# Microcontroller.net
KiCad netlist of a schematic drawn in Altium Designer
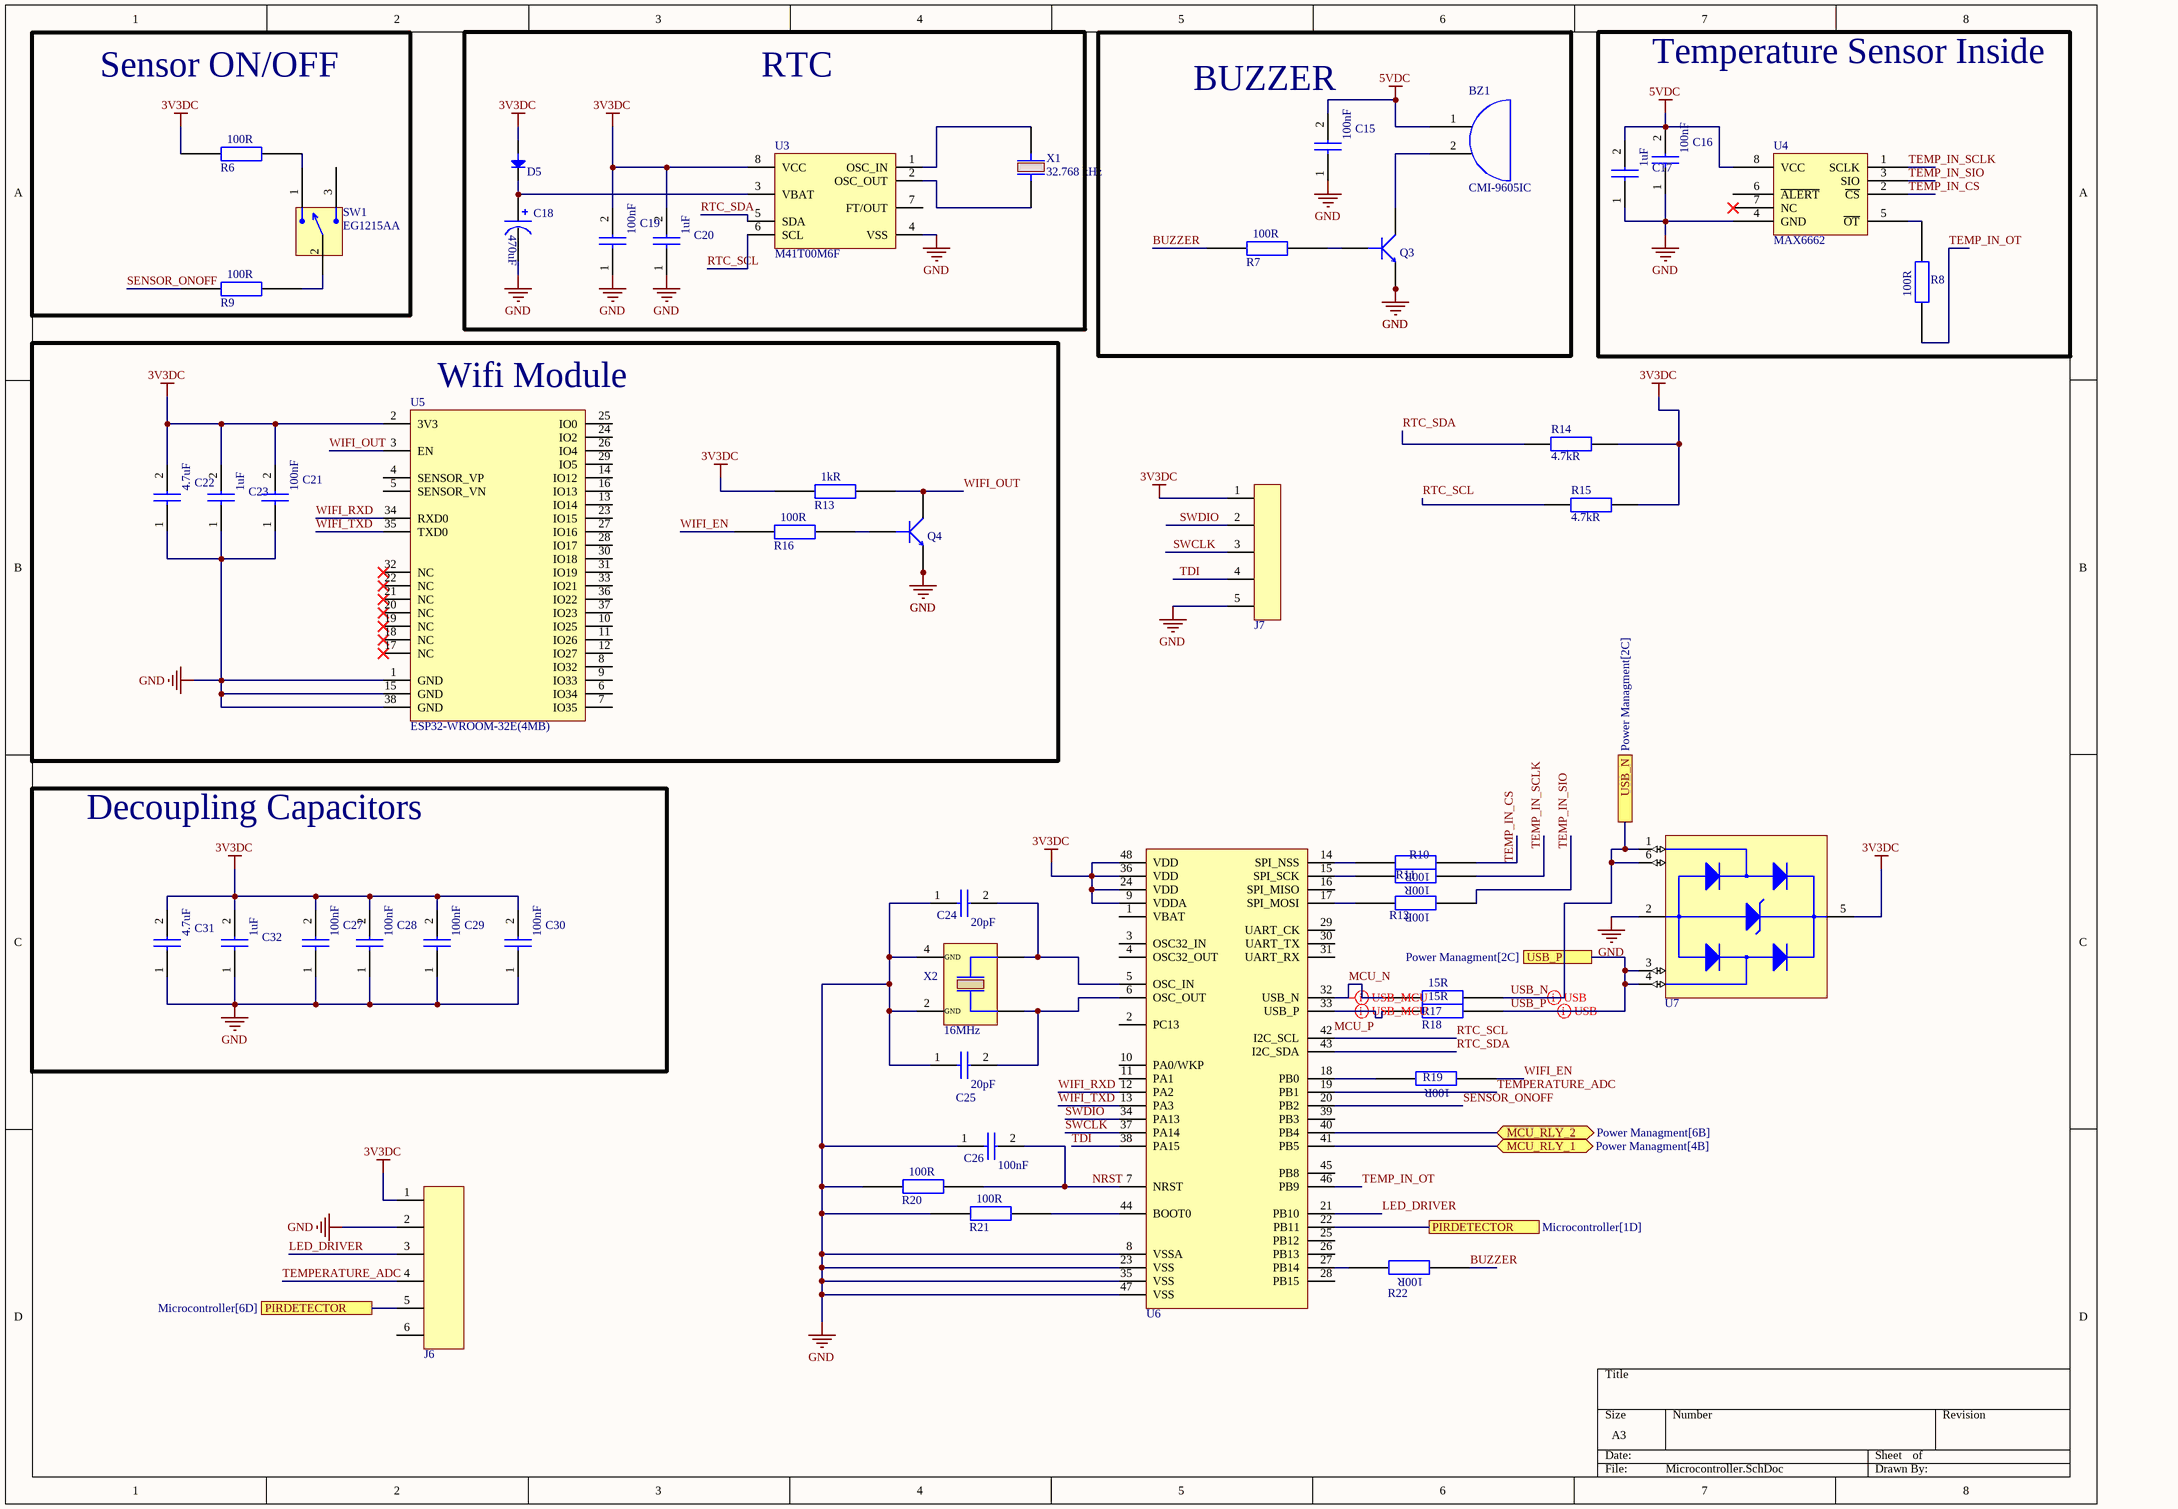
[diagram p0: Microcontroller.SchDoc]

(export (version "E")
  (design (tool "Eeschema 10.0.6"))
  (components
    (comp (ref "BZ1")
      (value "CMI-9605IC-0580T")
      (footprint "CMI-9605IC-0580T")
      (description "Audio Buzzer Magnetic 3VDC 7VDC 30mA 5VDC 85dB 2600Hz to 2800Hz Through Hole Pin Box")
      (fields
        (field (name "MANUFACTURER") "CUI Devices")
        (field (name "CASE/PACKAGE") "CMI-9605IC")
        (field (name "DEESIGNED BY") "Mert Ali Şentürl")
      )
      (libsource (lib "bowtie") (part "CMI-9605IC-0580T"))
    )
    (comp (ref "C15")
      (value "CL21B104KBCNNNC")
      (footprint "CAP_0805")
      (description "CAP CER 100nF %10 0603 SMD")
      (fields
        (field (name "MANUFACTURER") "Samsung")
        (field (name "TOLERANCE") "10%")
        (field (name "DESIGNED BY") "BERK")
      )
      (libsource (lib "bowtie") (part "CAP CER 0805 100nF %10"))
    )
    (comp (ref "C16")
      (value "CL21B104KBCNNNC")
      (footprint "CAP_0805")
      (description "CAP CER 100nF %10 0603 SMD")
      (fields
        (field (name "MANUFACTURER") "Samsung")
        (field (name "TOLERANCE") "10%")
        (field (name "DESIGNED BY") "BERK")
      )
      (libsource (lib "bowtie") (part "CAP CER 0805 100nF %10"))
    )
    (comp (ref "C17")
      (value "CL21B105KBFNNNE")
      (footprint "CAP_0805")
      (description "CAP CER 1uF %10 0805")
      (fields
        (field (name "MANUFACTURER") "Samsung")
        (field (name "TOLERANCE") "10%")
        (field (name "DESIGNED BY") "BERK")
      )
      (libsource (lib "bowtie") (part "CAP CER 0805 1uF %10"))
    )
    (comp (ref "C18")
      (value "CAP ALU ELEC 470uF 50V")
      (footprint "CAP_RADIAL_D10_P5")
      (description "Cap, 470UF, 50V, Alu Elec, Radial")
      (fields
        (field (name "MANUFACTURER") "KEMET")
        (field (name "MANUFACTURER PART NUMBER") "ESH477M050AH4AA")
        (field (name "DESIGNED BY") "Mert Ali Şentürk")
      )
      (libsource (lib "bowtie") (part "CAP ALU ELEC 470uF 50V"))
    )
    (comp (ref "C19")
      (value "CL21B104KBCNNNC")
      (footprint "CAP_0805")
      (description "CAP CER 100nF %10 0603 SMD")
      (fields
        (field (name "MANUFACTURER") "Samsung")
        (field (name "TOLERANCE") "10%")
        (field (name "DESIGNED BY") "BERK")
      )
      (libsource (lib "bowtie") (part "CAP CER 0805 100nF %10"))
    )
    (comp (ref "C20")
      (value "CL21B105KBFNNNE")
      (footprint "CAP_0805")
      (description "CAP CER 1uF %10 0805")
      (fields
        (field (name "MANUFACTURER") "Samsung")
        (field (name "TOLERANCE") "10%")
        (field (name "DESIGNED BY") "BERK")
      )
      (libsource (lib "bowtie") (part "CAP CER 0805 1uF %10"))
    )
    (comp (ref "C21")
      (value "CL21B104KBCNNNC")
      (footprint "CAP_0805")
      (description "CAP CER 100nF %10 0603 SMD")
      (fields
        (field (name "MANUFACTURER") "Samsung")
        (field (name "TOLERANCE") "10%")
        (field (name "DESIGNED BY") "BERK")
      )
      (libsource (lib "bowtie") (part "CAP CER 0805 100nF %10"))
    )
    (comp (ref "C22")
      (value "CL21A475KAQNNNE")
      (footprint "CAP_0805")
      (description "CAP CER 4.7uF %10 0805")
      (fields
        (field (name "MANUFACTURER") "Samsung")
        (field (name "TOLERANCE") "10%")
        (field (name "DESIGNED BY") "BERK")
      )
      (libsource (lib "bowtie") (part "CAP CER 0805 4.7uF %10"))
    )
    (comp (ref "C23")
      (value "CL21B105KBFNNNE")
      (footprint "CAP_0805")
      (description "CAP CER 1uF %10 0805")
      (fields
        (field (name "MANUFACTURER") "Samsung")
        (field (name "TOLERANCE") "10%")
        (field (name "DESIGNED BY") "BERK")
      )
      (libsource (lib "bowtie") (part "CAP CER 0805 1uF %10"))
    )
    (comp (ref "C24")
      (value "CL10C200JB8NNNC")
      (footprint "CAP_0603")
      (description "CAP CER 20pF %5 0603 SMD")
      (fields
        (field (name "MANUFACTURER") "Samsung")
        (field (name "TOLERANCE") "5%")
        (field (name "DESIGNED BY") "BERK")
      )
      (libsource (lib "bowtie") (part "CAP CER 0603 20pF %5"))
    )
    (comp (ref "C25")
      (value "CL10C200JB8NNNC")
      (footprint "CAP_0603")
      (description "CAP CER 20pF %5 0603 SMD")
      (fields
        (field (name "MANUFACTURER") "Samsung")
        (field (name "TOLERANCE") "5%")
        (field (name "DESIGNED BY") "BERK")
      )
      (libsource (lib "bowtie") (part "CAP CER 0603 20pF %5"))
    )
    (comp (ref "C26")
      (value "CL21B104KBCNNNC")
      (footprint "CAP_0805")
      (description "CAP CER 100nF %10 0603 SMD")
      (fields
        (field (name "MANUFACTURER") "Samsung")
        (field (name "TOLERANCE") "10%")
        (field (name "DESIGNED BY") "BERK")
      )
      (libsource (lib "bowtie") (part "CAP CER 0805 100nF %10"))
    )
    (comp (ref "C27")
      (value "CL21B104KBCNNNC")
      (footprint "CAP_0805")
      (description "CAP CER 100nF %10 0603 SMD")
      (fields
        (field (name "MANUFACTURER") "Samsung")
        (field (name "TOLERANCE") "10%")
        (field (name "DESIGNED BY") "BERK")
      )
      (libsource (lib "bowtie") (part "CAP CER 0805 100nF %10"))
    )
    (comp (ref "C28")
      (value "CL21B104KBCNNNC")
      (footprint "CAP_0805")
      (description "CAP CER 100nF %10 0603 SMD")
      (fields
        (field (name "MANUFACTURER") "Samsung")
        (field (name "TOLERANCE") "10%")
        (field (name "DESIGNED BY") "BERK")
      )
      (libsource (lib "bowtie") (part "CAP CER 0805 100nF %10"))
    )
    (comp (ref "C29")
      (value "CL21B104KBCNNNC")
      (footprint "CAP_0805")
      (description "CAP CER 100nF %10 0603 SMD")
      (fields
        (field (name "MANUFACTURER") "Samsung")
        (field (name "TOLERANCE") "10%")
        (field (name "DESIGNED BY") "BERK")
      )
      (libsource (lib "bowtie") (part "CAP CER 0805 100nF %10"))
    )
    (comp (ref "C30")
      (value "CL21B104KBCNNNC")
      (footprint "CAP_0805")
      (description "CAP CER 100nF %10 0603 SMD")
      (fields
        (field (name "MANUFACTURER") "Samsung")
        (field (name "TOLERANCE") "10%")
        (field (name "DESIGNED BY") "BERK")
      )
      (libsource (lib "bowtie") (part "CAP CER 0805 100nF %10"))
    )
    (comp (ref "C31")
      (value "CL21A475KAQNNNE")
      (footprint "CAP_0805")
      (description "CAP CER 4.7uF %10 0805")
      (fields
        (field (name "MANUFACTURER") "Samsung")
        (field (name "TOLERANCE") "10%")
        (field (name "DESIGNED BY") "BERK")
      )
      (libsource (lib "bowtie") (part "CAP CER 0805 4.7uF %10"))
    )
    (comp (ref "C32")
      (value "CL21B105KBFNNNE")
      (footprint "CAP_0805")
      (description "CAP CER 1uF %10 0805")
      (fields
        (field (name "MANUFACTURER") "Samsung")
        (field (name "TOLERANCE") "10%")
        (field (name "DESIGNED BY") "BERK")
      )
      (libsource (lib "bowtie") (part "CAP CER 0805 1uF %10"))
    )
    (comp (ref "D5")
      (value "1N4148WS")
      (footprint "SOD-323F")
      (description "Diode, Single, 75 V, 150 mA, 1 V, 4 ns")
      (fields
        (field (name "MANUFACTURER") "ON Semiconductor / Fairchild")
        (field (name "DESIGNED BY") "BERK")
      )
      (libsource (lib "bowtie") (part "1N4148WS"))
    )
    (comp (ref "J6")
      (value "64800611622")
      (footprint "64800611622")
      (description "1.50mm 6PIN Connector")
      (fields (field (name "MANUFACTURER") "Wurth Electronics"))
      (libsource (lib "bowtie") (part "64800611622_conn_6pin"))
    )
    (comp (ref "J7")
      (value "SMH-105-02-L-S")
      (footprint "PINHEADER1X5_RA")
      (description ".100 C.L. HORIZONTAL SMT SOCKET")
      (fields (field (name "MANUFACTURER") "Samtec") (field (name "DESIGNED BY") "BERK"))
      (libsource (lib "bowtie") (part "SMH-105-02-L-S"))
    )
    (comp (ref "Q3")
      (value "MMBT3904-7-F")
      (footprint "SOT23-F")
      (description "Transistor General Purpose BJT NPN 40 Volt 0.2A Automotive 3-Pin SOT-23")
      (fields (field (name "MANUFACTURER") "Diodes Zetex") (field (name "DESIGNED BY") "BERK"))
      (libsource (lib "bowtie") (part "MMBT3904-7-F"))
    )
    (comp (ref "Q4")
      (value "MMBT3904-7-F")
      (footprint "SOT23-F")
      (description "Transistor General Purpose BJT NPN 40 Volt 0.2A Automotive 3-Pin SOT-23")
      (fields (field (name "MANUFACTURER") "Diodes Zetex") (field (name "DESIGNED BY") "BERK"))
      (libsource (lib "bowtie") (part "MMBT3904-7-F"))
    )
    (comp (ref "R6")
      (value "RC0603JR-07100RL")
      (footprint "RES_0603")
      (description "RES 100 %5 OHM 0603 SMD")
      (fields
        (field (name "MANUFACTURER") "Yageo")
        (field (name "TOLERANCE") "5%")
        (field (name "DESIGNED BY") "BERK")
      )
      (libsource (lib "bowtie") (part "RES 0603 100R %5"))
    )
    (comp (ref "R7")
      (value "RC0603JR-07100RL")
      (footprint "RES_0603")
      (description "RES 100 %5 OHM 0603 SMD")
      (fields
        (field (name "MANUFACTURER") "Yageo")
        (field (name "TOLERANCE") "5%")
        (field (name "DESIGNED BY") "BERK")
      )
      (libsource (lib "bowtie") (part "RES 0603 100R %5"))
    )
    (comp (ref "R8")
      (value "RC0603JR-07100RL")
      (footprint "RES_0603")
      (description "RES 100 %5 OHM 0603 SMD")
      (fields
        (field (name "MANUFACTURER") "Yageo")
        (field (name "TOLERANCE") "5%")
        (field (name "DESIGNED BY") "BERK")
      )
      (libsource (lib "bowtie") (part "RES 0603 100R %5"))
    )
    (comp (ref "R9")
      (value "RC0603JR-07100RL")
      (footprint "RES_0603")
      (description "RES 100 %5 OHM 0603 SMD")
      (fields
        (field (name "MANUFACTURER") "Yageo")
        (field (name "TOLERANCE") "5%")
        (field (name "DESIGNED BY") "BERK")
      )
      (libsource (lib "bowtie") (part "RES 0603 100R %5"))
    )
    (comp (ref "R10")
      (value "RC0603JR-07100RL")
      (footprint "RES_0603")
      (description "RES 100 %5 OHM 0603 SMD")
      (fields
        (field (name "MANUFACTURER") "Yageo")
        (field (name "TOLERANCE") "5%")
        (field (name "DESIGNED BY") "BERK")
      )
      (libsource (lib "bowtie") (part "RES 0603 100R %5"))
    )
    (comp (ref "R11")
      (value "RC0603JR-07100RL")
      (footprint "RES_0603")
      (description "RES 100 %5 OHM 0603 SMD")
      (fields
        (field (name "MANUFACTURER") "Yageo")
        (field (name "TOLERANCE") "5%")
        (field (name "DESIGNED BY") "BERK")
      )
      (libsource (lib "bowtie") (part "RES 0603 100R %5"))
    )
    (comp (ref "R12")
      (value "RC0603JR-07100RL")
      (footprint "RES_0603")
      (description "RES 100 %5 OHM 0603 SMD")
      (fields
        (field (name "MANUFACTURER") "Yageo")
        (field (name "TOLERANCE") "5%")
        (field (name "DESIGNED BY") "BERK")
      )
      (libsource (lib "bowtie") (part "RES 0603 100R %5"))
    )
    (comp (ref "R13")
      (value "RC0603FR-0710KL")
      (footprint "RES_0603")
      (description "RES 1K %1 OHM 0603 SMD")
      (fields
        (field (name "MANUFACTURER") "Yageo")
        (field (name "MANUFACTURER PART NUMBER") "RC0603JR-071KL")
        (field (name "DESIGNED BY") "BERK")
      )
      (libsource (lib "bowtie") (part "RES 0603 1kR %1"))
    )
    (comp (ref "R14")
      (value "RC0603JR-074K7L")
      (footprint "RES_0603")
      (description "RES 4K7 %5 OHM 0603 SMD")
      (fields
        (field (name "MANUFACTURER") "Yageo")
        (field (name "TOLERANCE") "5%")
        (field (name "RESISTANCE") "4.7kR")
        (field (name "DESIGNED BY") "BERK")
      )
      (libsource (lib "bowtie") (part "RES 4K7 OHM 0603"))
    )
    (comp (ref "R15")
      (value "RC0603JR-074K7L")
      (footprint "RES_0603")
      (description "RES 4K7 %5 OHM 0603 SMD")
      (fields
        (field (name "MANUFACTURER") "Yageo")
        (field (name "TOLERANCE") "5%")
        (field (name "RESISTANCE") "4.7kR")
        (field (name "DESIGNED BY") "BERK")
      )
      (libsource (lib "bowtie") (part "RES 4K7 OHM 0603"))
    )
    (comp (ref "R16")
      (value "RC0603JR-07100RL")
      (footprint "RES_0603")
      (description "RES 100 %5 OHM 0603 SMD")
      (fields
        (field (name "MANUFACTURER") "Yageo")
        (field (name "TOLERANCE") "5%")
        (field (name "DESIGNED BY") "BERK")
      )
      (libsource (lib "bowtie") (part "RES 0603 100R %5"))
    )
    (comp (ref "R17")
      (value "RC0603JR-0715RL")
      (footprint "RES_0603")
      (description "RES 15 %5 OHM 0603 SMD")
      (fields
        (field (name "MANUFACTURER") "Yageo")
        (field (name "TOLERANCE") "5%")
        (field (name "DESIGNED BY") "BERK")
      )
      (libsource (lib "bowtie") (part "RES 0603 15R %5"))
    )
    (comp (ref "R18")
      (value "RC0603JR-0715RL")
      (footprint "RES_0603")
      (description "RES 15 %5 OHM 0603 SMD")
      (fields
        (field (name "MANUFACTURER") "Yageo")
        (field (name "TOLERANCE") "5%")
        (field (name "DESIGNED BY") "BERK")
      )
      (libsource (lib "bowtie") (part "RES 0603 15R %5"))
    )
    (comp (ref "R19")
      (value "RC0603JR-07100RL")
      (footprint "RES_0603")
      (description "RES 100 %5 OHM 0603 SMD")
      (fields
        (field (name "MANUFACTURER") "Yageo")
        (field (name "TOLERANCE") "5%")
        (field (name "DESIGNED BY") "BERK")
      )
      (libsource (lib "bowtie") (part "RES 0603 100R %5"))
    )
    (comp (ref "R20")
      (value "RC0603JR-07100RL")
      (footprint "RES_0603")
      (description "RES 100 %5 OHM 0603 SMD")
      (fields
        (field (name "MANUFACTURER") "Yageo")
        (field (name "TOLERANCE") "5%")
        (field (name "DESIGNED BY") "BERK")
      )
      (libsource (lib "bowtie") (part "RES 0603 100R %5"))
    )
    (comp (ref "R21")
      (value "RC0603JR-07100RL")
      (footprint "RES_0603")
      (description "RES 100 %5 OHM 0603 SMD")
      (fields
        (field (name "MANUFACTURER") "Yageo")
        (field (name "TOLERANCE") "5%")
        (field (name "DESIGNED BY") "BERK")
      )
      (libsource (lib "bowtie") (part "RES 0603 100R %5"))
    )
    (comp (ref "R22")
      (value "RC0603JR-07100RL")
      (footprint "RES_0603")
      (description "RES 100 %5 OHM 0603 SMD")
      (fields
        (field (name "MANUFACTURER") "Yageo")
        (field (name "TOLERANCE") "5%")
        (field (name "DESIGNED BY") "BERK")
      )
      (libsource (lib "bowtie") (part "RES 0603 100R %5"))
    )
    (comp (ref "SW1")
      (value "EG1215AA")
      (footprint "EG1215AA")
      (description "Slide Switch, SPDT, 0.025A, 24V, SMD")
      (fields (field (name "MANUFACTURER") "E-Switch") (field (name "DESIGNED BY") "Mert Ali Şentürk"))
      (libsource (lib "bowtie") (part "EG1215AA"))
    )
    (comp (ref "U3")
      (value "M41T00M6F")
      (footprint "SOIC-8")
      (description "Real-time Clocks Clock/Calendar I2C, 2-Wire Serial 70uA @ 2V ~ 5.5V SOIC-8_150mil RoHS")
      (fields
        (field (name "MANUFACTURER") "STMicroelectronics")
        (field (name "DESIGNED BY") "Mert Ali Şentürk")
      )
      (libsource (lib "bowtie") (part "M41T00M6F"))
    )
    (comp (ref "U4")
      (value "MAX6662")
      (footprint "SOIC-8")
      (description "Temp Sensor Digital Serial (3-Wire, SPI) 8-Pin SOIC N Tube")
      (fields
        (field (name "MANUFACTURER") "Maxim")
        (field (name "MANUFACTURER PART NUMBER") "MAX6662MSA+")
        (field (name "DESIGNED BY") "Mert Ali Şentürk")
      )
      (libsource (lib "bowtie") (part "MAX6662"))
    )
    (comp (ref "U5")
      (value "ESP32-WROOM-32E(4MB)")
      (footprint "ESP32WROOM32D/E")
      (description "SMD module, ESP32-D0WD-V3, ESP32 ECO V3, 4 MB SPI flash, PCB antenna")
      (fields
        (field (name "MANUFACTURER") "Espressif Systems")
        (field (name "MANUFACTURER PART NUMBER") "ESP32-WROOM-32E(M113EH3200PH3Q0)")
        (field (name "DESIGNED BY") "Mert Ali Şentürk")
      )
      (libsource (lib "bowtie") (part "ESP32-WROOM-32E(4MB)"))
    )
    (comp (ref "U6")
      (value "STM32F103C6T6A")
      (footprint "LQFP-48")
      (description "MCU 32-bit STM32F ARM Cortex M3 RISC 32KB Flash 2.5V/3.3V 48-Pin LQFP Tray")
      (fields
        (field (name "MANUFACTURER") "STMicroelectronics")
        (field (name "DESIGNED BY") "Mert Ali Şentürk")
      )
      (libsource (lib "bowtie") (part "STM32F103C6T6A"))
    )
    (comp (ref "U7")
      (value "USBLC6-2SC6")
      (footprint "SOT23-6L")
      (description "TVS DIODE 5.25V 17V SOT23-6")
      (fields (field (name "MANUFACTURER") "STMicroelectronics") (field (name "DESIGNED BY") "BERK"))
      (libsource (lib "bowtie") (part "USB PROTECTION"))
    )
    (comp (ref "X1")
      (value "ABS05-32.768KHZ-T")
      (footprint "ABS05")
      (description "Crystal, 32.768 kHz, SMD, 1.6mm x 1mm, 12.5 pF, 20 ppm, ABS05 Series")
      (fields
        (field (name "MANUFACTURER") "Abracon")
        (field (name "TOLERANCE") "20ppm")
        (field (name "OPERATING FREQUENCY") "32.768 kHz")
        (field (name "DESIGNED BY") "BERK")
      )
      (libsource (lib "bowtie") (part "CRYSTAL 32768kHZ"))
    )
    (comp (ref "X2")
      (value "ECS-160-20-30B-TR")
      (footprint "ECS")
      (description "CRYSTAL 16.0000MHZ 20PF SMD")
      (fields
        (field (name "MANUFACTURER") "ECS International")
        (field (name "TOLERANCE") "50ppm")
        (field (name "FREQUENCY") "16MHz")
        (field (name "DESIGNED BY") "BERK")
      )
      (libsource (lib "bowtie") (part "CRYSTAL 16MHz"))
    )
  )
  (nets
    (net (code "1") (name "/BUZZER") (class "Default")
      (node (ref "R22") (pin "1") (pinfunction "1_1") (pintype "passive"))
      (node (ref "R7") (pin "1") (pinfunction "1_1") (pintype "passive"))
    )
    (net (code "2") (name "/LED_DRIVER") (class "Default")
      (node (ref "J6") (pin "3") (pintype "power_in"))
      (node (ref "U6") (pin "21") (pinfunction "PB10_21") (pintype "passive"))
    )
    (net (code "3") (name "/MCU_N") (class "Default")
      (node (ref "R17") (pin "1") (pinfunction "1_1") (pintype "passive"))
      (node (ref "U6") (pin "32") (pinfunction "USB_N_32") (pintype "passive"))
    )
    (net (code "4") (name "/MCU_P") (class "Default")
      (node (ref "R18") (pin "1") (pinfunction "1_1") (pintype "passive"))
      (node (ref "U6") (pin "33") (pinfunction "USB_P_33") (pintype "passive"))
    )
    (net (code "5") (name "/MCU_RLY_1") (class "Default")
      (node (ref "U6") (pin "41") (pinfunction "PB5_41") (pintype "passive"))
    )
    (net (code "6") (name "/MCU_RLY_2") (class "Default")
      (node (ref "U6") (pin "40") (pinfunction "PB4_40") (pintype "passive"))
    )
    (net (code "7") (name "/NRST") (class "Default")
      (node (ref "C26") (pin "2") (pinfunction "2_2") (pintype "passive"))
      (node (ref "R20") (pin "2") (pinfunction "2_2") (pintype "passive"))
      (node (ref "U6") (pin "7") (pinfunction "NRST_7") (pintype "passive"))
    )
    (net (code "8") (name "/PIRDETECTOR") (class "Default")
      (node (ref "J6") (pin "5") (pintype "power_in"))
      (node (ref "U6") (pin "22") (pinfunction "PB11_22") (pintype "passive"))
    )
    (net (code "9") (name "/RTC_SCL") (class "Default")
      (node (ref "R15") (pin "1") (pinfunction "1_1") (pintype "passive"))
      (node (ref "U3") (pin "6") (pinfunction "SCL_6") (pintype "passive"))
      (node (ref "U6") (pin "42") (pinfunction "I2C_SCL_42") (pintype "passive"))
    )
    (net (code "10") (name "/RTC_SDA") (class "Default")
      (node (ref "R14") (pin "1") (pinfunction "1_1") (pintype "passive"))
      (node (ref "U3") (pin "5") (pinfunction "SDA_5") (pintype "passive"))
      (node (ref "U6") (pin "43") (pinfunction "I2C_SDA_43") (pintype "passive"))
    )
    (net (code "11") (name "/SENSOR_ONOFF") (class "Default")
      (node (ref "R9") (pin "1") (pinfunction "1_1") (pintype "passive"))
      (node (ref "U6") (pin "20") (pinfunction "PB2_20") (pintype "passive"))
    )
    (net (code "12") (name "/SWCLK") (class "Default")
      (node (ref "J7") (pin "3") (pinfunction "3_3") (pintype "power_in"))
      (node (ref "U6") (pin "37") (pinfunction "PA14_37") (pintype "passive"))
    )
    (net (code "13") (name "/SWDIO") (class "Default")
      (node (ref "J7") (pin "2") (pinfunction "2_2") (pintype "power_in"))
      (node (ref "U6") (pin "34") (pinfunction "PA13_34") (pintype "passive"))
    )
    (net (code "14") (name "/TDI") (class "Default")
      (node (ref "J7") (pin "4") (pinfunction "4_4") (pintype "power_in"))
      (node (ref "U6") (pin "38") (pinfunction "PA15_38") (pintype "passive"))
    )
    (net (code "15") (name "/TEMPERATURE_ADC") (class "Default")
      (node (ref "J6") (pin "4") (pintype "power_in"))
      (node (ref "U6") (pin "19") (pinfunction "PB1_19") (pintype "passive"))
    )
    (net (code "16") (name "/TEMP_IN_CS") (class "Default")
      (node (ref "R10") (pin "1") (pinfunction "1_1") (pintype "passive"))
      (node (ref "U4") (pin "2") (pinfunction "~{CS}_2") (pintype "passive"))
    )
    (net (code "17") (name "/TEMP_IN_OT") (class "Default")
      (node (ref "R8") (pin "1") (pinfunction "1_1") (pintype "passive"))
      (node (ref "U6") (pin "46") (pinfunction "PB9_46") (pintype "passive"))
    )
    (net (code "18") (name "/TEMP_IN_SCLK") (class "Default")
      (node (ref "R11") (pin "1") (pinfunction "1_1") (pintype "passive"))
      (node (ref "U4") (pin "1") (pinfunction "SCLK_1") (pintype "passive"))
    )
    (net (code "19") (name "/TEMP_IN_SIO") (class "Default")
      (node (ref "R12") (pin "1") (pinfunction "1_1") (pintype "passive"))
      (node (ref "U4") (pin "3") (pinfunction "SIO_3") (pintype "passive"))
    )
    (net (code "20") (name "/USB_N") (class "Default")
      (node (ref "R17") (pin "2") (pinfunction "2_2") (pintype "passive"))
      (node (ref "U7") (pin "1") (pinfunction "I/O1_1") (pintype "bidirectional"))
      (node (ref "U7") (pin "6") (pinfunction "I/O1_6") (pintype "bidirectional"))
    )
    (net (code "21") (name "/USB_P") (class "Default")
      (node (ref "R18") (pin "2") (pinfunction "2_2") (pintype "passive"))
      (node (ref "U7") (pin "3") (pinfunction "I/O2_3") (pintype "bidirectional"))
      (node (ref "U7") (pin "4") (pinfunction "I/O2_4") (pintype "bidirectional"))
    )
    (net (code "22") (name "/WIFI_EN") (class "Default")
      (node (ref "R16") (pin "1") (pinfunction "1_1") (pintype "passive"))
      (node (ref "R19") (pin "1") (pinfunction "1_1") (pintype "passive"))
    )
    (net (code "23") (name "/WIFI_OUT") (class "Default")
      (node (ref "Q4") (pin "3") (pinfunction "C_3") (pintype "power_in"))
      (node (ref "R13") (pin "2") (pinfunction "2_2") (pintype "passive"))
      (node (ref "U5") (pin "3") (pinfunction "EN_3") (pintype "passive"))
    )
    (net (code "24") (name "/WIFI_RXD") (class "Default")
      (node (ref "U5") (pin "34") (pinfunction "RXD0_34") (pintype "passive"))
      (node (ref "U6") (pin "12") (pinfunction "PA2_12") (pintype "passive"))
    )
    (net (code "25") (name "/WIFI_TXD") (class "Default")
      (node (ref "U5") (pin "35") (pinfunction "TXD0_35") (pintype "passive"))
      (node (ref "U6") (pin "13") (pinfunction "PA3_13") (pintype "passive"))
    )
    (net (code "26") (name "3V3DC") (class "Default")
      (node (ref "C19") (pin "2") (pinfunction "2_2") (pintype "passive"))
      (node (ref "C20") (pin "2") (pinfunction "2_2") (pintype "passive"))
      (node (ref "C21") (pin "2") (pinfunction "2_2") (pintype "passive"))
      (node (ref "C22") (pin "2") (pinfunction "2_2") (pintype "passive"))
      (node (ref "C23") (pin "2") (pinfunction "2_2") (pintype "passive"))
      (node (ref "C27") (pin "2") (pinfunction "2_2") (pintype "passive"))
      (node (ref "C28") (pin "2") (pinfunction "2_2") (pintype "passive"))
      (node (ref "C29") (pin "2") (pinfunction "2_2") (pintype "passive"))
      (node (ref "C30") (pin "2") (pinfunction "2_2") (pintype "passive"))
      (node (ref "C31") (pin "2") (pinfunction "2_2") (pintype "passive"))
      (node (ref "C32") (pin "2") (pinfunction "2_2") (pintype "passive"))
      (node (ref "D5") (pin "2") (pinfunction "2_2") (pintype "passive"))
      (node (ref "J6") (pin "1") (pintype "power_in"))
      (node (ref "J7") (pin "1") (pinfunction "1_1") (pintype "power_in"))
      (node (ref "R13") (pin "1") (pinfunction "1_1") (pintype "passive"))
      (node (ref "R14") (pin "2") (pinfunction "2_2") (pintype "passive"))
      (node (ref "R15") (pin "2") (pinfunction "2_2") (pintype "passive"))
      (node (ref "R6") (pin "1") (pinfunction "1_1") (pintype "passive"))
      (node (ref "U3") (pin "8") (pinfunction "VCC_8") (pintype "passive"))
      (node (ref "U5") (pin "2") (pinfunction "3V3_2") (pintype "passive"))
      (node (ref "U6") (pin "24") (pinfunction "VDD_24") (pintype "passive"))
      (node (ref "U6") (pin "36") (pinfunction "VDD_36") (pintype "passive"))
      (node (ref "U6") (pin "48") (pinfunction "VDD_48") (pintype "passive"))
      (node (ref "U6") (pin "9") (pinfunction "VDDA_9") (pintype "passive"))
      (node (ref "U7") (pin "5") (pinfunction "VBUS_5") (pintype "power_in"))
    )
    (net (code "27") (name "5VDC") (class "Default")
      (node (ref "BZ1") (pin "1") (pinfunction "1_1") (pintype "passive"))
      (node (ref "C15") (pin "2") (pinfunction "2_2") (pintype "passive"))
      (node (ref "C16") (pin "2") (pinfunction "2_2") (pintype "passive"))
      (node (ref "C17") (pin "2") (pinfunction "2_2") (pintype "passive"))
      (node (ref "U4") (pin "8") (pinfunction "VCC_8") (pintype "passive"))
    )
    (net (code "28") (name "GND") (class "Default")
      (node (ref "C15") (pin "1") (pinfunction "1_1") (pintype "passive"))
      (node (ref "C16") (pin "1") (pinfunction "1_1") (pintype "passive"))
      (node (ref "C17") (pin "1") (pinfunction "1_1") (pintype "passive"))
      (node (ref "C18") (pin "2") (pinfunction "2_2") (pintype "passive"))
      (node (ref "C19") (pin "1") (pinfunction "1_1") (pintype "passive"))
      (node (ref "C20") (pin "1") (pinfunction "1_1") (pintype "passive"))
      (node (ref "C21") (pin "1") (pinfunction "1_1") (pintype "passive"))
      (node (ref "C22") (pin "1") (pinfunction "1_1") (pintype "passive"))
      (node (ref "C23") (pin "1") (pinfunction "1_1") (pintype "passive"))
      (node (ref "C24") (pin "1") (pinfunction "1_1") (pintype "passive"))
      (node (ref "C25") (pin "1") (pinfunction "1_1") (pintype "passive"))
      (node (ref "C26") (pin "1") (pinfunction "1_1") (pintype "passive"))
      (node (ref "C27") (pin "1") (pinfunction "1_1") (pintype "passive"))
      (node (ref "C28") (pin "1") (pinfunction "1_1") (pintype "passive"))
      (node (ref "C29") (pin "1") (pinfunction "1_1") (pintype "passive"))
      (node (ref "C30") (pin "1") (pinfunction "1_1") (pintype "passive"))
      (node (ref "C31") (pin "1") (pinfunction "1_1") (pintype "passive"))
      (node (ref "C32") (pin "1") (pinfunction "1_1") (pintype "passive"))
      (node (ref "J6") (pin "2") (pintype "power_in"))
      (node (ref "J7") (pin "5") (pinfunction "5_5") (pintype "power_in"))
      (node (ref "Q3") (pin "2") (pinfunction "E_2") (pintype "power_in"))
      (node (ref "Q4") (pin "2") (pinfunction "E_2") (pintype "power_in"))
      (node (ref "R20") (pin "1") (pinfunction "1_1") (pintype "passive"))
      (node (ref "R21") (pin "1") (pinfunction "1_1") (pintype "passive"))
      (node (ref "U3") (pin "4") (pinfunction "VSS_4") (pintype "passive"))
      (node (ref "U4") (pin "4") (pinfunction "GND_4") (pintype "passive"))
      (node (ref "U5") (pin "1") (pinfunction "GND_1") (pintype "passive"))
      (node (ref "U5") (pin "15") (pinfunction "GND_15") (pintype "passive"))
      (node (ref "U5") (pin "38") (pinfunction "GND_38") (pintype "passive"))
      (node (ref "U6") (pin "23") (pinfunction "VSS_23") (pintype "passive"))
      (node (ref "U6") (pin "35") (pinfunction "VSS_35") (pintype "passive"))
      (node (ref "U6") (pin "47") (pinfunction "VSS_47") (pintype "passive"))
      (node (ref "U6") (pin "8") (pinfunction "VSSA_8") (pintype "passive"))
      (node (ref "U7") (pin "2") (pinfunction "GND_2") (pintype "power_in"))
      (node (ref "X2") (pin "2") (pinfunction "GND_2") (pintype "passive"))
      (node (ref "X2") (pin "4") (pinfunction "GND_4") (pintype "passive"))
    )
    (net (code "29") (name "Net-(Q3-B)") (class "Default")
      (node (ref "Q3") (pin "1") (pinfunction "B_1") (pintype "power_in"))
      (node (ref "R7") (pin "2") (pinfunction "2_2") (pintype "passive"))
    )
    (net (code "30") (name "Net-(Q3-C)") (class "Default")
      (node (ref "BZ1") (pin "2") (pinfunction "2_2") (pintype "passive"))
      (node (ref "Q3") (pin "3") (pinfunction "C_3") (pintype "power_in"))
    )
    (net (code "31") (name "Net-(Q4-B)") (class "Default")
      (node (ref "Q4") (pin "1") (pinfunction "B_1") (pintype "power_in"))
      (node (ref "R16") (pin "2") (pinfunction "2_2") (pintype "passive"))
    )
    (net (code "32") (name "Net-(R6-Pad2)") (class "Default")
      (node (ref "R6") (pin "2") (pinfunction "2_2") (pintype "passive"))
      (node (ref "SW1") (pin "1") (pinfunction "1_1") (pintype "passive"))
    )
    (net (code "33") (name "Net-(R9-Pad2)") (class "Default")
      (node (ref "R9") (pin "2") (pinfunction "2_2") (pintype "passive"))
      (node (ref "SW1") (pin "2") (pinfunction "2_2") (pintype "passive"))
    )
    (net (code "34") (name "Net-(U3-OSC_IN)") (class "Default")
      (node (ref "U3") (pin "1") (pinfunction "OSC_IN_1") (pintype "passive"))
      (node (ref "X1") (pin "2") (pinfunction "2_2") (pintype "passive"))
    )
    (net (code "35") (name "Net-(U3-OSC_OUT)") (class "Default")
      (node (ref "U3") (pin "2") (pinfunction "OSC_OUT_2") (pintype "passive"))
      (node (ref "X1") (pin "1") (pinfunction "1_1") (pintype "passive"))
    )
    (net (code "36") (name "Net-(U3-VBAT)") (class "Default")
      (node (ref "C18") (pin "1") (pinfunction "1_1") (pintype "passive"))
      (node (ref "D5") (pin "1") (pinfunction "1_1") (pintype "passive"))
      (node (ref "U3") (pin "3") (pinfunction "VBAT_3") (pintype "passive"))
    )
    (net (code "37") (name "Net-(U4-~{OT})") (class "Default")
      (node (ref "R8") (pin "2") (pinfunction "2_2") (pintype "passive"))
      (node (ref "U4") (pin "5") (pinfunction "~{OT}_5") (pintype "passive"))
    )
    (net (code "38") (name "Net-(U6-BOOT0)") (class "Default")
      (node (ref "R21") (pin "2") (pinfunction "2_2") (pintype "passive"))
      (node (ref "U6") (pin "44") (pinfunction "BOOT0_44") (pintype "passive"))
    )
    (net (code "39") (name "Net-(U6-OSC_IN)") (class "Default")
      (node (ref "C24") (pin "2") (pinfunction "2_2") (pintype "passive"))
      (node (ref "U6") (pin "5") (pinfunction "OSC_IN_5") (pintype "passive"))
      (node (ref "X2") (pin "3") (pinfunction "3_3") (pintype "passive"))
    )
    (net (code "40") (name "Net-(U6-OSC_OUT)") (class "Default")
      (node (ref "C25") (pin "2") (pinfunction "2_2") (pintype "passive"))
      (node (ref "U6") (pin "6") (pinfunction "OSC_OUT_6") (pintype "passive"))
      (node (ref "X2") (pin "1") (pinfunction "1_1") (pintype "passive"))
    )
    (net (code "41") (name "Net-(U6-PB0)") (class "Default")
      (node (ref "R19") (pin "2") (pinfunction "2_2") (pintype "passive"))
      (node (ref "U6") (pin "18") (pinfunction "PB0_18") (pintype "passive"))
    )
    (net (code "42") (name "Net-(U6-PB14)") (class "Default")
      (node (ref "R22") (pin "2") (pinfunction "2_2") (pintype "passive"))
      (node (ref "U6") (pin "27") (pinfunction "PB14_27") (pintype "passive"))
    )
    (net (code "43") (name "Net-(U6-SPI_MOSI)") (class "Default")
      (node (ref "R12") (pin "2") (pinfunction "2_2") (pintype "passive"))
      (node (ref "U6") (pin "17") (pinfunction "SPI_MOSI_17") (pintype "passive"))
    )
    (net (code "44") (name "Net-(U6-SPI_NSS)") (class "Default")
      (node (ref "R10") (pin "2") (pinfunction "2_2") (pintype "passive"))
      (node (ref "U6") (pin "14") (pinfunction "SPI_NSS_14") (pintype "passive"))
    )
    (net (code "45") (name "Net-(U6-SPI_SCK)") (class "Default")
      (node (ref "R11") (pin "2") (pinfunction "2_2") (pintype "passive"))
      (node (ref "U6") (pin "15") (pinfunction "SPI_SCK_15") (pintype "passive"))
    )
    (net (code "46") (name "unconnected-(J6-Pad6)") (class "Default")
      (node (ref "J6") (pin "6") (pintype "power_in"))
    )
    (net (code "47") (name "unconnected-(SW1-Pad3)") (class "Default")
      (node (ref "SW1") (pin "3") (pinfunction "3_3") (pintype "passive"))
    )
    (net (code "48") (name "unconnected-(U3-FT{slash}OUT-Pad7)") (class "Default")
      (node (ref "U3") (pin "7") (pinfunction "FT/OUT_7") (pintype "passive"))
    )
    (net (code "49") (name "unconnected-(U4-NC-Pad7)") (class "Default")
      (node (ref "U4") (pin "7") (pinfunction "NC_7") (pintype "passive+no_connect"))
    )
    (net (code "50") (name "unconnected-(U4-~{ALERT}-Pad6)") (class "Default")
      (node (ref "U4") (pin "6") (pinfunction "~{ALERT}_6") (pintype "passive"))
    )
    (net (code "51") (name "unconnected-(U5-IO0-Pad25)") (class "Default")
      (node (ref "U5") (pin "25") (pinfunction "IO0_25") (pintype "passive"))
    )
    (net (code "52") (name "unconnected-(U5-IO2-Pad24)") (class "Default")
      (node (ref "U5") (pin "24") (pinfunction "IO2_24") (pintype "passive"))
    )
    (net (code "53") (name "unconnected-(U5-IO4-Pad26)") (class "Default")
      (node (ref "U5") (pin "26") (pinfunction "IO4_26") (pintype "passive"))
    )
    (net (code "54") (name "unconnected-(U5-IO5-Pad29)") (class "Default")
      (node (ref "U5") (pin "29") (pinfunction "IO5_29") (pintype "passive"))
    )
    (net (code "55") (name "unconnected-(U5-IO12-Pad14)") (class "Default")
      (node (ref "U5") (pin "14") (pinfunction "IO12_14") (pintype "passive"))
    )
    (net (code "56") (name "unconnected-(U5-IO13-Pad16)") (class "Default")
      (node (ref "U5") (pin "16") (pinfunction "IO13_16") (pintype "passive"))
    )
    (net (code "57") (name "unconnected-(U5-IO14-Pad13)") (class "Default")
      (node (ref "U5") (pin "13") (pinfunction "IO14_13") (pintype "passive"))
    )
    (net (code "58") (name "unconnected-(U5-IO15-Pad23)") (class "Default")
      (node (ref "U5") (pin "23") (pinfunction "IO15_23") (pintype "passive"))
    )
    (net (code "59") (name "unconnected-(U5-IO16-Pad27)") (class "Default")
      (node (ref "U5") (pin "27") (pinfunction "IO16_27") (pintype "passive"))
    )
    (net (code "60") (name "unconnected-(U5-IO17-Pad28)") (class "Default")
      (node (ref "U5") (pin "28") (pinfunction "IO17_28") (pintype "passive"))
    )
    (net (code "61") (name "unconnected-(U5-IO18-Pad30)") (class "Default")
      (node (ref "U5") (pin "30") (pinfunction "IO18_30") (pintype "passive"))
    )
    (net (code "62") (name "unconnected-(U5-IO19-Pad31)") (class "Default")
      (node (ref "U5") (pin "31") (pinfunction "IO19_31") (pintype "passive"))
    )
    (net (code "63") (name "unconnected-(U5-IO21-Pad33)") (class "Default")
      (node (ref "U5") (pin "33") (pinfunction "IO21_33") (pintype "passive"))
    )
    (net (code "64") (name "unconnected-(U5-IO22-Pad36)") (class "Default")
      (node (ref "U5") (pin "36") (pinfunction "IO22_36") (pintype "passive"))
    )
    (net (code "65") (name "unconnected-(U5-IO23-Pad37)") (class "Default")
      (node (ref "U5") (pin "37") (pinfunction "IO23_37") (pintype "passive"))
    )
    (net (code "66") (name "unconnected-(U5-IO25-Pad10)") (class "Default")
      (node (ref "U5") (pin "10") (pinfunction "IO25_10") (pintype "passive"))
    )
    (net (code "67") (name "unconnected-(U5-IO26-Pad11)") (class "Default")
      (node (ref "U5") (pin "11") (pinfunction "IO26_11") (pintype "passive"))
    )
    (net (code "68") (name "unconnected-(U5-IO27-Pad12)") (class "Default")
      (node (ref "U5") (pin "12") (pinfunction "IO27_12") (pintype "passive"))
    )
    (net (code "69") (name "unconnected-(U5-IO32-Pad8)") (class "Default")
      (node (ref "U5") (pin "8") (pinfunction "IO32_8") (pintype "passive"))
    )
    (net (code "70") (name "unconnected-(U5-IO33-Pad9)") (class "Default")
      (node (ref "U5") (pin "9") (pinfunction "IO33_9") (pintype "passive"))
    )
    (net (code "71") (name "unconnected-(U5-IO34-Pad6)") (class "Default")
      (node (ref "U5") (pin "6") (pinfunction "IO34_6") (pintype "passive"))
    )
    (net (code "72") (name "unconnected-(U5-IO35-Pad7)") (class "Default")
      (node (ref "U5") (pin "7") (pinfunction "IO35_7") (pintype "passive"))
    )
    (net (code "73") (name "unconnected-(U5-NC-Pad17)") (class "Default")
      (node (ref "U5") (pin "17") (pinfunction "NC_17") (pintype "passive+no_connect"))
    )
    (net (code "74") (name "unconnected-(U5-NC-Pad18)") (class "Default")
      (node (ref "U5") (pin "18") (pinfunction "NC_18") (pintype "passive+no_connect"))
    )
    (net (code "75") (name "unconnected-(U5-NC-Pad19)") (class "Default")
      (node (ref "U5") (pin "19") (pinfunction "NC_19") (pintype "passive+no_connect"))
    )
    (net (code "76") (name "unconnected-(U5-NC-Pad20)") (class "Default")
      (node (ref "U5") (pin "20") (pinfunction "NC_20") (pintype "passive+no_connect"))
    )
    (net (code "77") (name "unconnected-(U5-NC-Pad21)") (class "Default")
      (node (ref "U5") (pin "21") (pinfunction "NC_21") (pintype "passive+no_connect"))
    )
    (net (code "78") (name "unconnected-(U5-NC-Pad22)") (class "Default")
      (node (ref "U5") (pin "22") (pinfunction "NC_22") (pintype "passive+no_connect"))
    )
    (net (code "79") (name "unconnected-(U5-NC-Pad32)") (class "Default")
      (node (ref "U5") (pin "32") (pinfunction "NC_32") (pintype "passive+no_connect"))
    )
    (net (code "80") (name "unconnected-(U5-SENSOR_VN-Pad5)") (class "Default")
      (node (ref "U5") (pin "5") (pinfunction "SENSOR_VN_5") (pintype "passive"))
    )
    (net (code "81") (name "unconnected-(U5-SENSOR_VP-Pad4)") (class "Default")
      (node (ref "U5") (pin "4") (pinfunction "SENSOR_VP_4") (pintype "passive"))
    )
    (net (code "82") (name "unconnected-(U6-OSC32_IN-Pad3)") (class "Default")
      (node (ref "U6") (pin "3") (pinfunction "OSC32_IN_3") (pintype "passive"))
    )
    (net (code "83") (name "unconnected-(U6-OSC32_OUT-Pad4)") (class "Default")
      (node (ref "U6") (pin "4") (pinfunction "OSC32_OUT_4") (pintype "passive"))
    )
    (net (code "84") (name "unconnected-(U6-PA0{slash}WKP-Pad10)") (class "Default")
      (node (ref "U6") (pin "10") (pinfunction "PA0/WKP_10") (pintype "passive"))
    )
    (net (code "85") (name "unconnected-(U6-PA1-Pad11)") (class "Default")
      (node (ref "U6") (pin "11") (pinfunction "PA1_11") (pintype "passive"))
    )
    (net (code "86") (name "unconnected-(U6-PB3-Pad39)") (class "Default")
      (node (ref "U6") (pin "39") (pinfunction "PB3_39") (pintype "passive"))
    )
    (net (code "87") (name "unconnected-(U6-PB8-Pad45)") (class "Default")
      (node (ref "U6") (pin "45") (pinfunction "PB8_45") (pintype "passive"))
    )
    (net (code "88") (name "unconnected-(U6-PB12-Pad25)") (class "Default")
      (node (ref "U6") (pin "25") (pinfunction "PB12_25") (pintype "passive"))
    )
    (net (code "89") (name "unconnected-(U6-PB13-Pad26)") (class "Default")
      (node (ref "U6") (pin "26") (pinfunction "PB13_26") (pintype "passive"))
    )
    (net (code "90") (name "unconnected-(U6-PB15-Pad28)") (class "Default")
      (node (ref "U6") (pin "28") (pinfunction "PB15_28") (pintype "passive"))
    )
    (net (code "91") (name "unconnected-(U6-PC13-Pad2)") (class "Default")
      (node (ref "U6") (pin "2") (pinfunction "PC13_2") (pintype "passive"))
    )
    (net (code "92") (name "unconnected-(U6-SPI_MISO-Pad16)") (class "Default")
      (node (ref "U6") (pin "16") (pinfunction "SPI_MISO_16") (pintype "passive"))
    )
    (net (code "93") (name "unconnected-(U6-UART_CK-Pad29)") (class "Default")
      (node (ref "U6") (pin "29") (pinfunction "UART_CK_29") (pintype "passive"))
    )
    (net (code "94") (name "unconnected-(U6-UART_RX-Pad31)") (class "Default")
      (node (ref "U6") (pin "31") (pinfunction "UART_RX_31") (pintype "passive"))
    )
    (net (code "95") (name "unconnected-(U6-UART_TX-Pad30)") (class "Default")
      (node (ref "U6") (pin "30") (pinfunction "UART_TX_30") (pintype "passive"))
    )
    (net (code "96") (name "unconnected-(U6-VBAT-Pad1)") (class "Default")
      (node (ref "U6") (pin "1") (pinfunction "VBAT_1") (pintype "passive"))
    )
  )
)
